# current_amplifier_03.net
KiCad netlist of a schematic drawn in Altium Designer
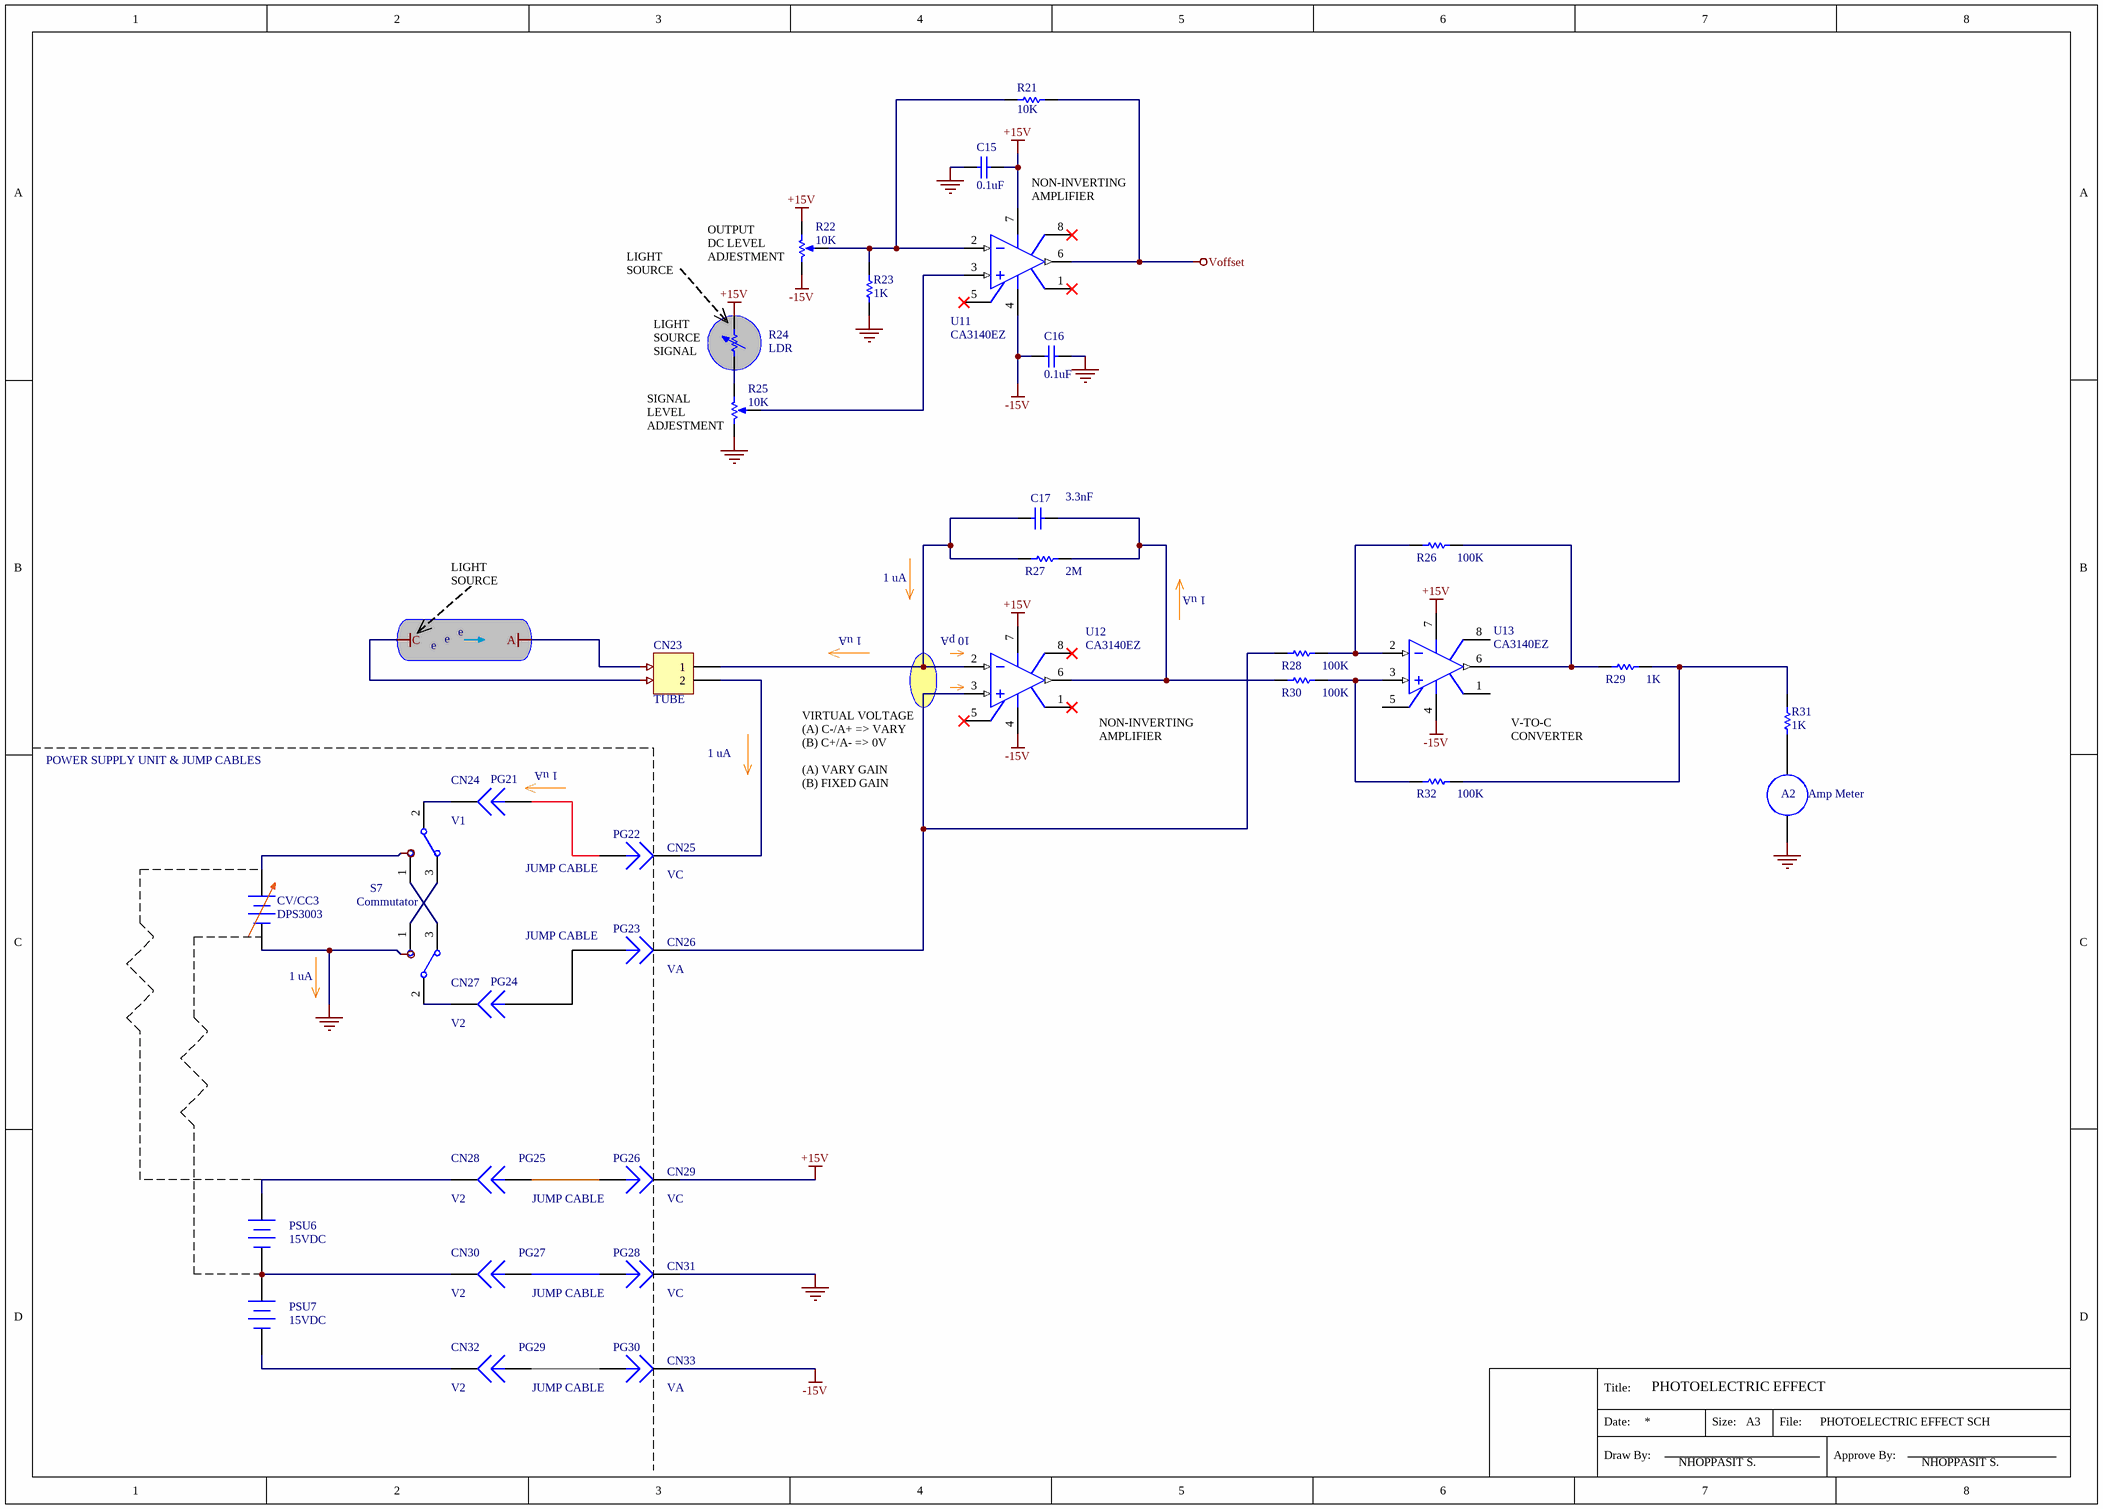
[diagram p0: current amplifier 03.SchDoc]

(export (version "E")
  (design (tool "Eeschema 10.0.6"))
  (components
    (comp (ref "A2")
      (value "Amp Meter")
      (footprint "RAD-0.1")
      (description "Indicating Instrument")
      (fields (field (name "PUBLISHER") "Altium Limited"))
      (libsource (lib "Miscellaneous Devices") (part "Meter"))
    )
    (comp (ref "C15")
      (value "0.1uF")
      (footprint "RAD-0.3")
      (description "Capacitor")
      (fields (field (name "PUBLISHER") "Altium Limited"))
      (libsource (lib "Miscellaneous Devices") (part "Cap"))
    )
    (comp (ref "C16")
      (value "0.1uF")
      (footprint "RAD-0.3")
      (description "Capacitor")
      (fields (field (name "PUBLISHER") "Altium Limited"))
      (libsource (lib "Miscellaneous Devices") (part "Cap"))
    )
    (comp (ref "C17")
      (value "3.3nF")
      (footprint "RAD-0.3")
      (description "Capacitor")
      (fields (field (name "PUBLISHER") "Altium Limited"))
      (libsource (lib "Miscellaneous Devices") (part "Cap"))
    )
    (comp (ref "CN23")
      (value "TUBE")
      (footprint "HDR1X2")
      (description "Header, 2-Pin")
      (fields (field (name "PUBLISHER") "Altium Limited"))
      (libsource (lib "Miscellaneous Connectors") (part "Header 2"))
    )
    (comp (ref "CN24")
      (value "V1")
      (footprint "PIN1")
      (description "Socket")
      (fields (field (name "PUBLISHER") "Altium Limited"))
      (libsource (lib "Miscellaneous Connectors") (part "Socket"))
    )
    (comp (ref "CN25")
      (value "VC")
      (footprint "PIN1")
      (description "Socket")
      (fields (field (name "PUBLISHER") "Altium Limited"))
      (libsource (lib "Miscellaneous Connectors") (part "Socket"))
    )
    (comp (ref "CN26")
      (value "VA")
      (footprint "PIN1")
      (description "Socket")
      (fields (field (name "PUBLISHER") "Altium Limited"))
      (libsource (lib "Miscellaneous Connectors") (part "Socket"))
    )
    (comp (ref "CN27")
      (value "V2")
      (footprint "PIN1")
      (description "Socket")
      (fields (field (name "PUBLISHER") "Altium Limited"))
      (libsource (lib "Miscellaneous Connectors") (part "Socket"))
    )
    (comp (ref "CN28")
      (value "V2")
      (footprint "PIN1")
      (description "Socket")
      (fields (field (name "PUBLISHER") "Altium Limited"))
      (libsource (lib "Miscellaneous Connectors") (part "Socket"))
    )
    (comp (ref "CN29")
      (value "VC")
      (footprint "PIN1")
      (description "Socket")
      (fields (field (name "PUBLISHER") "Altium Limited"))
      (libsource (lib "Miscellaneous Connectors") (part "Socket"))
    )
    (comp (ref "CN30")
      (value "V2")
      (footprint "PIN1")
      (description "Socket")
      (fields (field (name "PUBLISHER") "Altium Limited"))
      (libsource (lib "Miscellaneous Connectors") (part "Socket"))
    )
    (comp (ref "CN31")
      (value "VC")
      (footprint "PIN1")
      (description "Socket")
      (fields (field (name "PUBLISHER") "Altium Limited"))
      (libsource (lib "Miscellaneous Connectors") (part "Socket"))
    )
    (comp (ref "CN32")
      (value "V2")
      (footprint "PIN1")
      (description "Socket")
      (fields (field (name "PUBLISHER") "Altium Limited"))
      (libsource (lib "Miscellaneous Connectors") (part "Socket"))
    )
    (comp (ref "CN33")
      (value "VA")
      (footprint "PIN1")
      (description "Socket")
      (fields (field (name "PUBLISHER") "Altium Limited"))
      (libsource (lib "Miscellaneous Connectors") (part "Socket"))
    )
    (comp (ref "CV/CC3")
      (value "DPS3003")
      (footprint "BAT-2")
      (description "Multicell Battery")
      (fields (field (name "PUBLISHER") "Altium Limited"))
      (libsource (lib "Miscellaneous Devices") (part "Battery"))
    )
    (comp (ref "PG21")
      (value "Plug")
      (footprint "PIN1")
      (fields (field (name "PUBLISHER") "Altium Limited"))
      (libsource (lib "Miscellaneous Connectors") (part "Plug"))
    )
    (comp (ref "PG22")
      (value "Plug")
      (footprint "PIN1")
      (fields (field (name "PUBLISHER") "Altium Limited"))
      (libsource (lib "Miscellaneous Connectors") (part "Plug"))
    )
    (comp (ref "PG23")
      (value "Plug")
      (footprint "PIN1")
      (fields (field (name "PUBLISHER") "Altium Limited"))
      (libsource (lib "Miscellaneous Connectors") (part "Plug"))
    )
    (comp (ref "PG24")
      (value "Plug")
      (footprint "PIN1")
      (fields (field (name "PUBLISHER") "Altium Limited"))
      (libsource (lib "Miscellaneous Connectors") (part "Plug"))
    )
    (comp (ref "PG25")
      (value "Plug")
      (footprint "PIN1")
      (fields (field (name "PUBLISHER") "Altium Limited"))
      (libsource (lib "Miscellaneous Connectors") (part "Plug"))
    )
    (comp (ref "PG26")
      (value "Plug")
      (footprint "PIN1")
      (fields (field (name "PUBLISHER") "Altium Limited"))
      (libsource (lib "Miscellaneous Connectors") (part "Plug"))
    )
    (comp (ref "PG27")
      (value "Plug")
      (footprint "PIN1")
      (fields (field (name "PUBLISHER") "Altium Limited"))
      (libsource (lib "Miscellaneous Connectors") (part "Plug"))
    )
    (comp (ref "PG28")
      (value "Plug")
      (footprint "PIN1")
      (fields (field (name "PUBLISHER") "Altium Limited"))
      (libsource (lib "Miscellaneous Connectors") (part "Plug"))
    )
    (comp (ref "PG29")
      (value "Plug")
      (footprint "PIN1")
      (fields (field (name "PUBLISHER") "Altium Limited"))
      (libsource (lib "Miscellaneous Connectors") (part "Plug"))
    )
    (comp (ref "PG30")
      (value "Plug")
      (footprint "PIN1")
      (fields (field (name "PUBLISHER") "Altium Limited"))
      (libsource (lib "Miscellaneous Connectors") (part "Plug"))
    )
    (comp (ref "PSU6")
      (value "15VDC")
      (footprint "BAT-2")
      (description "Multicell Battery")
      (fields (field (name "PUBLISHER") "Altium Limited"))
      (libsource (lib "Miscellaneous Devices") (part "Battery"))
    )
    (comp (ref "PSU7")
      (value "15VDC")
      (footprint "BAT-2")
      (description "Multicell Battery")
      (fields (field (name "PUBLISHER") "Altium Limited"))
      (libsource (lib "Miscellaneous Devices") (part "Battery"))
    )
    (comp (ref "R21")
      (value "10K")
      (footprint "AXIAL-0.3")
      (description "Resistor")
      (fields (field (name "PUBLISHER") "Altium Limited"))
      (libsource (lib "Miscellaneous Devices") (part "Res1"))
    )
    (comp (ref "R22")
      (value "10K")
      (footprint "VR5")
      (description "Potentiometer")
      (fields (field (name "PUBLISHER") "Altium Limited"))
      (libsource (lib "Miscellaneous Devices") (part "RPot"))
    )
    (comp (ref "R23")
      (value "1K")
      (footprint "AXIAL-0.3")
      (description "Resistor")
      (fields (field (name "PUBLISHER") "Altium Limited"))
      (libsource (lib "Miscellaneous Devices") (part "Res1"))
    )
    (comp (ref "R24")
      (value "LDR")
      (footprint "AXIAL-0.7")
      (description "Variable Resistor")
      (fields (field (name "PUBLISHER") "Altium Limited"))
      (libsource (lib "Miscellaneous Devices") (part "Res Adj1"))
    )
    (comp (ref "R25")
      (value "10K")
      (footprint "VR5")
      (description "Potentiometer")
      (fields (field (name "PUBLISHER") "Altium Limited"))
      (libsource (lib "Miscellaneous Devices") (part "RPot"))
    )
    (comp (ref "R26")
      (value "100K")
      (footprint "AXIAL-0.3")
      (description "Resistor")
      (fields (field (name "PUBLISHER") "Altium Limited"))
      (libsource (lib "Miscellaneous Devices") (part "Res1"))
    )
    (comp (ref "R27")
      (value "2M")
      (footprint "AXIAL-0.3")
      (description "Resistor")
      (fields (field (name "PUBLISHER") "Altium Limited"))
      (libsource (lib "Miscellaneous Devices") (part "Res1"))
    )
    (comp (ref "R28")
      (value "100K")
      (footprint "AXIAL-0.3")
      (description "Resistor")
      (fields (field (name "PUBLISHER") "Altium Limited"))
      (libsource (lib "Miscellaneous Devices") (part "Res1"))
    )
    (comp (ref "R29")
      (value "1K")
      (footprint "AXIAL-0.3")
      (description "Resistor")
      (fields (field (name "PUBLISHER") "Altium Limited"))
      (libsource (lib "Miscellaneous Devices") (part "Res1"))
    )
    (comp (ref "R30")
      (value "100K")
      (footprint "AXIAL-0.3")
      (description "Resistor")
      (fields (field (name "PUBLISHER") "Altium Limited"))
      (libsource (lib "Miscellaneous Devices") (part "Res1"))
    )
    (comp (ref "R31")
      (value "1K")
      (footprint "AXIAL-0.3")
      (description "Resistor")
      (fields (field (name "PUBLISHER") "Altium Limited"))
      (libsource (lib "Miscellaneous Devices") (part "Res1"))
    )
    (comp (ref "R32")
      (value "100K")
      (footprint "AXIAL-0.3")
      (description "Resistor")
      (fields (field (name "PUBLISHER") "Altium Limited"))
      (libsource (lib "Miscellaneous Devices") (part "Res1"))
    )
    (comp (ref "S7")
      (value "Commutator")
      (footprint "TL36WW15050")
      (description "SPDT Subminiature Toggle Switch, Right Angle Mounting, Vertical Actuation")
      (fields (field (name "PUBLISHER") "Altium Limited"))
      (libsource (lib "Miscellaneous Devices") (part "SW-SPDT"))
    )
    (comp (ref "S8")
      (value "SW-SPDT")
      (footprint "TL36WW15050")
      (description "SPDT Subminiature Toggle Switch, Right Angle Mounting, Vertical Actuation")
      (fields (field (name "PUBLISHER") "Altium Limited"))
      (libsource (lib "Miscellaneous Devices") (part "SW-SPDT"))
    )
    (comp (ref "U11")
      (value "CA3140EZ")
      (footprint "H-08A")
      (description "FET Operational Amplifier")
      (fields (field (name "PUBLISHER") "Altium Limited"))
      (libsource (lib "Miscellaneous Devices") (part "Op Amp"))
    )
    (comp (ref "U12")
      (value "CA3140EZ")
      (footprint "H-08A")
      (description "FET Operational Amplifier")
      (fields (field (name "PUBLISHER") "Altium Limited"))
      (libsource (lib "Miscellaneous Devices") (part "Op Amp"))
    )
    (comp (ref "U13")
      (value "CA3140EZ")
      (footprint "H-08A")
      (description "FET Operational Amplifier")
      (fields (field (name "PUBLISHER") "Altium Limited"))
      (libsource (lib "Miscellaneous Devices") (part "Op Amp"))
    )
  )
  (nets
    (net (code "1") (name "+15V") (class "Default")
      (node (ref "C15") (pin "2") (pinfunction "2_2") (pintype "passive"))
      (node (ref "CN29") (pin "1") (pinfunction "1_1") (pintype "passive"))
      (node (ref "R22") (pin "1") (pinfunction "TOP_1") (pintype "passive"))
      (node (ref "R24") (pin "2") (pinfunction "2_2") (pintype "passive"))
      (node (ref "U11") (pin "7") (pinfunction "V+_7") (pintype "power_in"))
      (node (ref "U12") (pin "7") (pinfunction "V+_7") (pintype "power_in"))
      (node (ref "U13") (pin "7") (pinfunction "V+_7") (pintype "power_in"))
    )
    (net (code "2") (name "-15V") (class "Default")
      (node (ref "C16") (pin "1") (pinfunction "1_1") (pintype "passive"))
      (node (ref "CN33") (pin "1") (pinfunction "1_1") (pintype "passive"))
      (node (ref "R22") (pin "2") (pinfunction "BOT_2") (pintype "passive"))
      (node (ref "U11") (pin "4") (pinfunction "V-_4") (pintype "power_in"))
      (node (ref "U12") (pin "4") (pinfunction "V-_4") (pintype "power_in"))
      (node (ref "U13") (pin "4") (pinfunction "V-_4") (pintype "power_in"))
    )
    (net (code "3") (name "A") (class "Default")
      (node (ref "A2") (pin "1") (pinfunction "1_1") (pintype "passive"))
      (node (ref "C15") (pin "1") (pinfunction "1_1") (pintype "passive"))
      (node (ref "C16") (pin "2") (pinfunction "2_2") (pintype "passive"))
      (node (ref "CN31") (pin "1") (pinfunction "1_1") (pintype "passive"))
      (node (ref "CV/CC3") (pin "1") (pinfunction "+_1") (pintype "passive"))
      (node (ref "CV/CC3") (pin "2") (pinfunction "-_2") (pintype "passive"))
      (node (ref "R23") (pin "1") (pinfunction "1_1") (pintype "passive"))
      (node (ref "R25") (pin "2") (pinfunction "BOT_2") (pintype "passive"))
    )
    (net (code "4") (name "Net-(A2-Pad2)") (class "Default")
      (node (ref "A2") (pin "2") (pinfunction "2_2") (pintype "passive"))
      (node (ref "R31") (pin "1") (pinfunction "1_1") (pintype "passive"))
    )
    (net (code "5") (name "Net-(CN23-Pad2)") (class "Default")
      (node (ref "CN23") (pin "2") (pinfunction "2_2") (pintype "passive"))
      (node (ref "CN25") (pin "1") (pinfunction "1_1") (pintype "passive"))
    )
    (net (code "6") (name "Net-(CN24-Pad1)") (class "Default")
      (node (ref "CN24") (pin "1") (pinfunction "1_1") (pintype "passive"))
      (node (ref "S7") (pin "2") (pinfunction "2_2") (pintype "passive"))
    )
    (net (code "7") (name "Net-(CN27-Pad1)") (class "Default")
      (node (ref "CN27") (pin "1") (pinfunction "1_1") (pintype "passive"))
      (node (ref "S8") (pin "2") (pinfunction "2_2") (pintype "passive"))
    )
    (net (code "8") (name "Net-(PG21-Pad1)") (class "Default")
      (node (ref "PG21") (pin "1") (pinfunction "1_1") (pintype "passive"))
      (node (ref "PG22") (pin "1") (pinfunction "1_1") (pintype "passive"))
    )
    (net (code "9") (name "Net-(PG23-Pad1)") (class "Default")
      (node (ref "PG23") (pin "1") (pinfunction "1_1") (pintype "passive"))
      (node (ref "PG24") (pin "1") (pinfunction "1_1") (pintype "passive"))
    )
    (net (code "10") (name "Net-(PG25-Pad1)") (class "Default")
      (node (ref "PG25") (pin "1") (pinfunction "1_1") (pintype "passive"))
      (node (ref "PG26") (pin "1") (pinfunction "1_1") (pintype "passive"))
    )
    (net (code "11") (name "Net-(PG27-Pad1)") (class "Default")
      (node (ref "PG27") (pin "1") (pinfunction "1_1") (pintype "passive"))
      (node (ref "PG28") (pin "1") (pinfunction "1_1") (pintype "passive"))
    )
    (net (code "12") (name "Net-(PG29-Pad1)") (class "Default")
      (node (ref "PG29") (pin "1") (pinfunction "1_1") (pintype "passive"))
      (node (ref "PG30") (pin "1") (pinfunction "1_1") (pintype "passive"))
    )
    (net (code "13") (name "Net-(PSU6-+)") (class "Default")
      (node (ref "CN28") (pin "1") (pinfunction "1_1") (pintype "passive"))
      (node (ref "PSU6") (pin "1") (pinfunction "+_1") (pintype "passive"))
    )
    (net (code "14") (name "Net-(PSU6--)") (class "Default")
      (node (ref "CN30") (pin "1") (pinfunction "1_1") (pintype "passive"))
      (node (ref "PSU6") (pin "2") (pinfunction "-_2") (pintype "passive"))
      (node (ref "PSU7") (pin "1") (pinfunction "+_1") (pintype "passive"))
    )
    (net (code "15") (name "Net-(PSU7--)") (class "Default")
      (node (ref "CN32") (pin "1") (pinfunction "1_1") (pintype "passive"))
      (node (ref "PSU7") (pin "2") (pinfunction "-_2") (pintype "passive"))
    )
    (net (code "16") (name "Net-(R22-TAP)") (class "Default")
      (node (ref "R21") (pin "1") (pinfunction "1_1") (pintype "passive"))
      (node (ref "R22") (pin "3") (pinfunction "TAP_3") (pintype "passive"))
      (node (ref "R23") (pin "2") (pinfunction "2_2") (pintype "passive"))
      (node (ref "U11") (pin "2") (pinfunction "IN-_2") (pintype "input"))
    )
    (net (code "17") (name "Net-(R25-TAP)") (class "Default")
      (node (ref "R25") (pin "3") (pinfunction "TAP_3") (pintype "passive"))
      (node (ref "U11") (pin "3") (pinfunction "IN+_3") (pintype "input"))
    )
    (net (code "18") (name "Net-(R25-TOP)") (class "Default")
      (node (ref "R24") (pin "1") (pinfunction "1_1") (pintype "passive"))
      (node (ref "R25") (pin "1") (pinfunction "TOP_1") (pintype "passive"))
    )
    (net (code "19") (name "Net-(R29-Pad2)") (class "Default")
      (node (ref "R29") (pin "2") (pinfunction "2_2") (pintype "passive"))
      (node (ref "R31") (pin "2") (pinfunction "2_2") (pintype "passive"))
      (node (ref "R32") (pin "2") (pinfunction "2_2") (pintype "passive"))
    )
    (net (code "20") (name "Net-(S7-Pad1)") (class "Default")
      (node (ref "S7") (pin "1") (pinfunction "1_1") (pintype "passive"))
      (node (ref "S8") (pin "3") (pinfunction "3_3") (pintype "passive"))
    )
    (net (code "21") (name "Net-(S7-Pad3)") (class "Default")
      (node (ref "S7") (pin "3") (pinfunction "3_3") (pintype "passive"))
      (node (ref "S8") (pin "1") (pinfunction "1_1") (pintype "passive"))
    )
    (net (code "22") (name "Net-(U12-IN+)") (class "Default")
      (node (ref "CN26") (pin "1") (pinfunction "1_1") (pintype "passive"))
      (node (ref "R28") (pin "1") (pinfunction "1_1") (pintype "passive"))
      (node (ref "U12") (pin "3") (pinfunction "IN+_3") (pintype "input"))
    )
    (net (code "23") (name "Net-(U12-IN-)") (class "Default")
      (node (ref "C17") (pin "1") (pinfunction "1_1") (pintype "passive"))
      (node (ref "CN23") (pin "1") (pinfunction "1_1") (pintype "passive"))
      (node (ref "R27") (pin "1") (pinfunction "1_1") (pintype "passive"))
      (node (ref "U12") (pin "2") (pinfunction "IN-_2") (pintype "input"))
    )
    (net (code "24") (name "Net-(U12-OUT)") (class "Default")
      (node (ref "C17") (pin "2") (pinfunction "2_2") (pintype "passive"))
      (node (ref "R27") (pin "2") (pinfunction "2_2") (pintype "passive"))
      (node (ref "R30") (pin "1") (pinfunction "1_1") (pintype "passive"))
      (node (ref "U12") (pin "6") (pinfunction "OUT_6") (pintype "output"))
    )
    (net (code "25") (name "Net-(U13-IN+)") (class "Default")
      (node (ref "R30") (pin "2") (pinfunction "2_2") (pintype "passive"))
      (node (ref "R32") (pin "1") (pinfunction "1_1") (pintype "passive"))
      (node (ref "U13") (pin "3") (pinfunction "IN+_3") (pintype "input"))
    )
    (net (code "26") (name "Net-(U13-IN-)") (class "Default")
      (node (ref "R26") (pin "1") (pinfunction "1_1") (pintype "passive"))
      (node (ref "R28") (pin "2") (pinfunction "2_2") (pintype "passive"))
      (node (ref "U13") (pin "2") (pinfunction "IN-_2") (pintype "input"))
    )
    (net (code "27") (name "Net-(U13-OUT)") (class "Default")
      (node (ref "R26") (pin "2") (pinfunction "2_2") (pintype "passive"))
      (node (ref "R29") (pin "1") (pinfunction "1_1") (pintype "passive"))
      (node (ref "U13") (pin "6") (pinfunction "OUT_6") (pintype "output"))
    )
    (net (code "28") (name "Voffset") (class "Default")
      (node (ref "R21") (pin "2") (pinfunction "2_2") (pintype "passive"))
      (node (ref "U11") (pin "6") (pinfunction "OUT_6") (pintype "output"))
    )
    (net (code "29") (name "unconnected-(U11-OS_NUL-Pad1)") (class "Default")
      (node (ref "U11") (pin "1") (pinfunction "OS_NUL_1") (pintype "passive+no_connect"))
    )
    (net (code "30") (name "unconnected-(U11-OS_NUL-Pad5)") (class "Default")
      (node (ref "U11") (pin "5") (pinfunction "OS_NUL_5") (pintype "passive+no_connect"))
    )
    (net (code "31") (name "unconnected-(U11-TAB-Pad8)") (class "Default")
      (node (ref "U11") (pin "8") (pinfunction "TAB_8") (pintype "passive+no_connect"))
    )
    (net (code "32") (name "unconnected-(U12-OS_NUL-Pad1)") (class "Default")
      (node (ref "U12") (pin "1") (pinfunction "OS_NUL_1") (pintype "passive+no_connect"))
    )
    (net (code "33") (name "unconnected-(U12-OS_NUL-Pad5)") (class "Default")
      (node (ref "U12") (pin "5") (pinfunction "OS_NUL_5") (pintype "passive+no_connect"))
    )
    (net (code "34") (name "unconnected-(U12-TAB-Pad8)") (class "Default")
      (node (ref "U12") (pin "8") (pinfunction "TAB_8") (pintype "passive+no_connect"))
    )
    (net (code "35") (name "unconnected-(U13-OS_NUL-Pad1)") (class "Default")
      (node (ref "U13") (pin "1") (pinfunction "OS_NUL_1") (pintype "passive"))
    )
    (net (code "36") (name "unconnected-(U13-OS_NUL-Pad5)") (class "Default")
      (node (ref "U13") (pin "5") (pinfunction "OS_NUL_5") (pintype "passive"))
    )
    (net (code "37") (name "unconnected-(U13-TAB-Pad8)") (class "Default")
      (node (ref "U13") (pin "8") (pinfunction "TAB_8") (pintype "passive"))
    )
  )
)
